# board.net
KiCad netlist of a schematic drawn in EAGLE
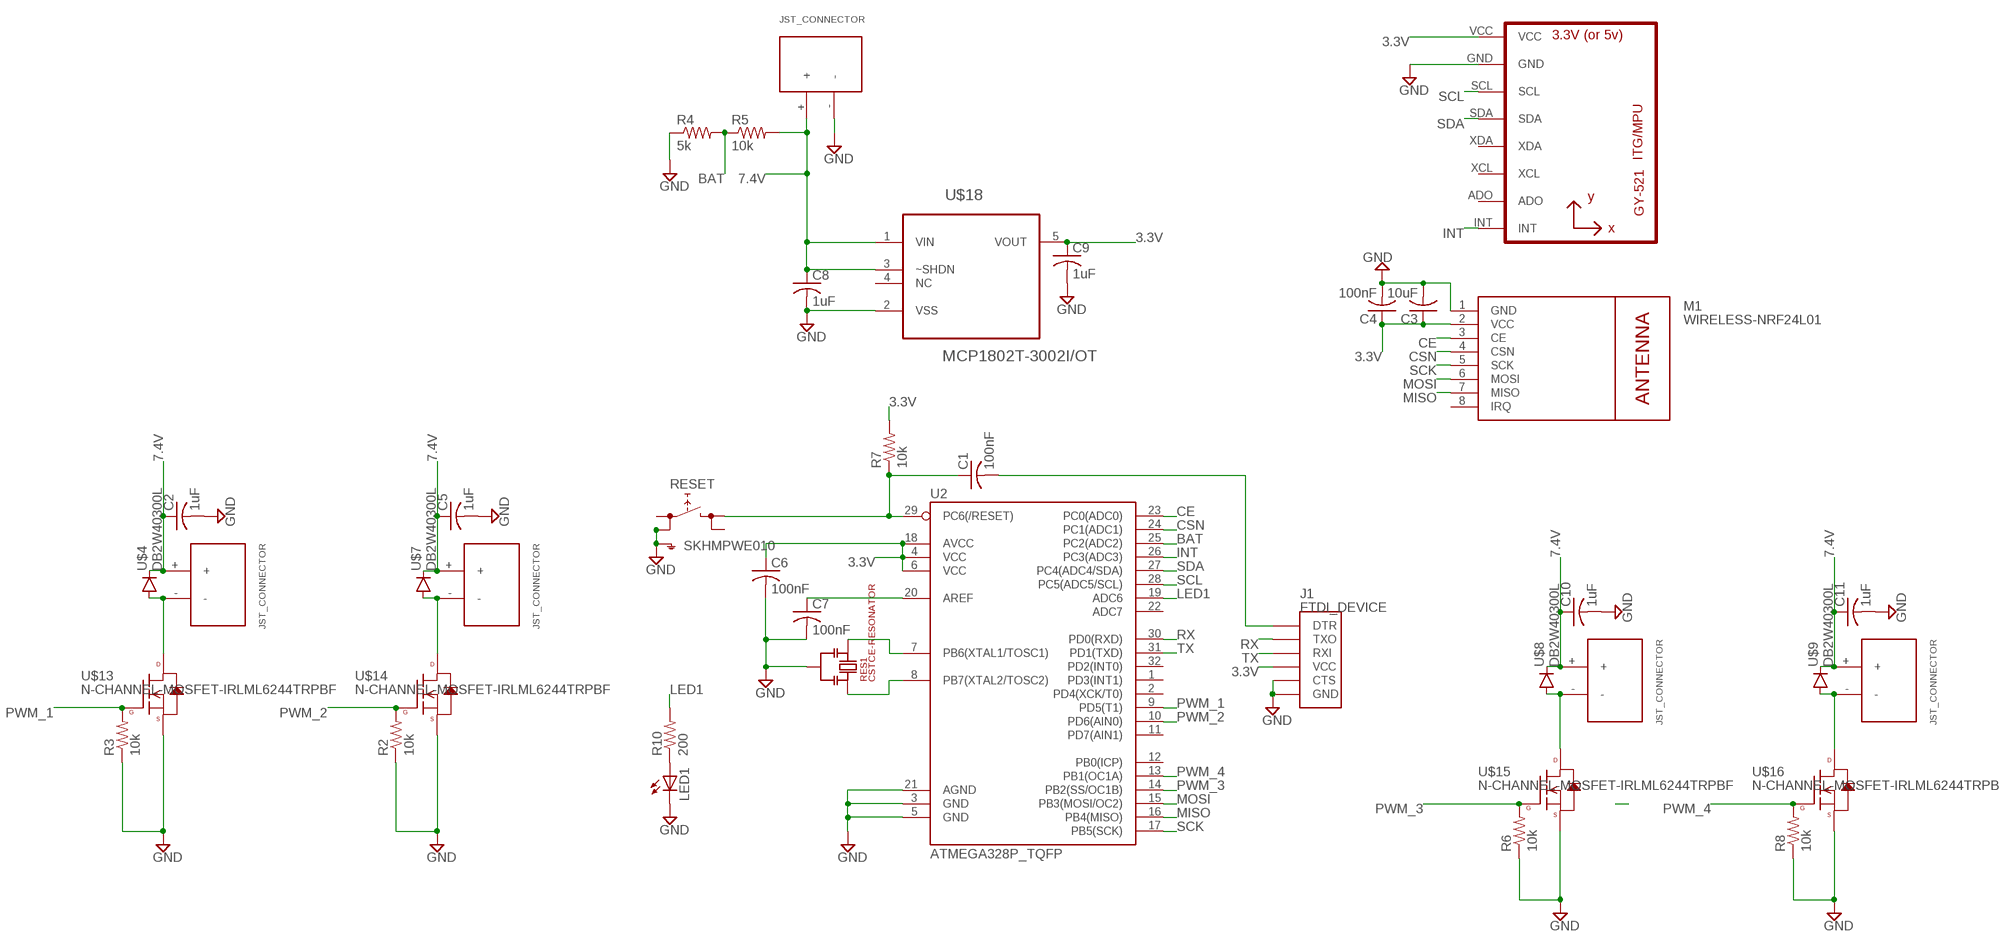
[diagram p0: schematic, sheet 1]

(export (version "E")
  (design (tool "Eeschema 10.0.6"))
  (components
    (comp (ref "C1")
      (value "100nF")
      (footprint "eagle-import:C0603")
      (libsource (lib "eagle-import") (part "C-USC0603"))
    )
    (comp (ref "C2")
      (value "1uF")
      (footprint "eagle-import:C0603")
      (libsource (lib "eagle-import") (part "C-USC0603"))
    )
    (comp (ref "C3")
      (value "10uF")
      (footprint "eagle-import:C0603")
      (libsource (lib "eagle-import") (part "C-USC0603"))
    )
    (comp (ref "C4")
      (value "100nF")
      (footprint "eagle-import:C0603")
      (libsource (lib "eagle-import") (part "C-USC0603"))
    )
    (comp (ref "C5")
      (value "1uF")
      (footprint "eagle-import:C0603")
      (libsource (lib "eagle-import") (part "C-USC0603"))
    )
    (comp (ref "C6")
      (value "100nF")
      (footprint "eagle-import:C0603")
      (libsource (lib "eagle-import") (part "C-USC0603"))
    )
    (comp (ref "C7")
      (value "100nF")
      (footprint "eagle-import:C0603")
      (libsource (lib "eagle-import") (part "C-USC0603"))
    )
    (comp (ref "C8")
      (value "1uF")
      (footprint "eagle-import:C0603")
      (libsource (lib "eagle-import") (part "C-USC0603"))
    )
    (comp (ref "C9")
      (value "1uF")
      (footprint "eagle-import:C0603")
      (libsource (lib "eagle-import") (part "C-USC0603"))
    )
    (comp (ref "C10")
      (value "1uF")
      (footprint "eagle-import:C0603")
      (libsource (lib "eagle-import") (part "C-USC0603"))
    )
    (comp (ref "C11")
      (value "1uF")
      (footprint "eagle-import:C0603")
      (libsource (lib "eagle-import") (part "C-USC0603"))
    )
    (comp (ref "J1")
      (value "FTDI_DEVICE")
      (footprint "eagle-import:FTDI_DEVICE_SIDE")
      (libsource (lib "eagle-import") (part "FTDI_DEVICE"))
    )
    (comp (ref "LED1")
      (value "LEDCHIP-LED0603")
      (footprint "eagle-import:CHIP-LED0603")
      (libsource (lib "eagle-import") (part "LEDCHIP-LED0603"))
    )
    (comp (ref "M1")
      (value "WIRELESS-NRF24L01")
      (footprint "eagle-import:WIRELESS-NRF24L01")
      (libsource (lib "eagle-import") (part "WIRELESS-NRF24L01"))
    )
    (comp (ref "R2")
      (value "10k")
      (footprint "eagle-import:R0603")
      (libsource (lib "eagle-import") (part "R-US_R0603"))
    )
    (comp (ref "R3")
      (value "10k")
      (footprint "eagle-import:R0603")
      (libsource (lib "eagle-import") (part "R-US_R0603"))
    )
    (comp (ref "R4")
      (value "5k")
      (footprint "eagle-import:R0603")
      (libsource (lib "eagle-import") (part "R-US_R0603"))
    )
    (comp (ref "R5")
      (value "10k")
      (footprint "eagle-import:R0603")
      (libsource (lib "eagle-import") (part "R-US_R0603"))
    )
    (comp (ref "R6")
      (value "10k")
      (footprint "eagle-import:R0603")
      (libsource (lib "eagle-import") (part "R-US_R0603"))
    )
    (comp (ref "R7")
      (value "10k")
      (footprint "eagle-import:R0603")
      (libsource (lib "eagle-import") (part "R-US_R0603"))
    )
    (comp (ref "R8")
      (value "10k")
      (footprint "eagle-import:R0603")
      (libsource (lib "eagle-import") (part "R-US_R0603"))
    )
    (comp (ref "R10")
      (value "200")
      (footprint "eagle-import:R0603")
      (libsource (lib "eagle-import") (part "R-US_R0603"))
    )
    (comp (ref "RES1")
      (value "CSTCE-RESONATOR")
      (footprint "eagle-import:CSTCE16M0V53-R0")
      (libsource (lib "eagle-import") (part "CSTCE-RESONATOR"))
    )
    (comp (ref "RESET")
      (value "SKHMPWE010")
      (footprint "eagle-import:SKHMPXE010")
      (libsource (lib "eagle-import") (part "SKHMPE010W"))
    )
    (comp (ref "U$3")
      (value "JST_CONNECTOR_FEMALE")
      (footprint "eagle-import:JST_CONNECTOR_FEMALE")
      (libsource (lib "eagle-import") (part "JST_CONNECTOR_FEMALE"))
    )
    (comp (ref "U$4")
      (value "DB2W40300L")
      (footprint "eagle-import:MINI2-F3-B")
      (libsource (lib "eagle-import") (part "DB2W40300L"))
    )
    (comp (ref "U$7")
      (value "DB2W40300L")
      (footprint "eagle-import:MINI2-F3-B")
      (libsource (lib "eagle-import") (part "DB2W40300L"))
    )
    (comp (ref "U$8")
      (value "DB2W40300L")
      (footprint "eagle-import:MINI2-F3-B")
      (libsource (lib "eagle-import") (part "DB2W40300L"))
    )
    (comp (ref "U$9")
      (value "DB2W40300L")
      (footprint "eagle-import:MINI2-F3-B")
      (libsource (lib "eagle-import") (part "DB2W40300L"))
    )
    (comp (ref "U$10")
      (value "JST_CONNECTOR_FEMALE")
      (footprint "eagle-import:JST_CONNECTOR_FEMALE")
      (libsource (lib "eagle-import") (part "JST_CONNECTOR_FEMALE"))
    )
    (comp (ref "U$11")
      (value "JST_CONNECTOR_FEMALE")
      (footprint "eagle-import:JST_CONNECTOR_FEMALE")
      (libsource (lib "eagle-import") (part "JST_CONNECTOR_FEMALE"))
    )
    (comp (ref "U$12")
      (value "JST_CONNECTOR_FEMALE")
      (footprint "eagle-import:JST_CONNECTOR_FEMALE")
      (libsource (lib "eagle-import") (part "JST_CONNECTOR_FEMALE"))
    )
    (comp (ref "U$13")
      (value "N-CHANNEL-MOSFET-IRLML6244TRPBF")
      (footprint "eagle-import:SOT23-3")
      (libsource (lib "eagle-import") (part "N-CHANNEL-MOSFET-IRLML6244TRPBF"))
    )
    (comp (ref "U$14")
      (value "N-CHANNEL-MOSFET-IRLML6244TRPBF")
      (footprint "eagle-import:SOT23-3")
      (libsource (lib "eagle-import") (part "N-CHANNEL-MOSFET-IRLML6244TRPBF"))
    )
    (comp (ref "U$15")
      (value "N-CHANNEL-MOSFET-IRLML6244TRPBF")
      (footprint "eagle-import:SOT23-3")
      (libsource (lib "eagle-import") (part "N-CHANNEL-MOSFET-IRLML6244TRPBF"))
    )
    (comp (ref "U$16")
      (value "N-CHANNEL-MOSFET-IRLML6244TRPBF")
      (footprint "eagle-import:SOT23-3")
      (libsource (lib "eagle-import") (part "N-CHANNEL-MOSFET-IRLML6244TRPBF"))
    )
    (comp (ref "U$17")
      (value "JST_CONNECTOR_FEMALE")
      (footprint "eagle-import:JST_CONNECTOR_FEMALE")
      (libsource (lib "eagle-import") (part "JST_CONNECTOR_FEMALE"))
    )
    (comp (ref "U$18")
      (value "MCP1802T-3002I/OT")
      (footprint "eagle-import:SOT95P270X145-5N")
      (libsource (lib "eagle-import") (part "MCP1802T-3002I/OT"))
    )
    (comp (ref "U1")
      (value "GY-521MPU6050")
      (footprint "eagle-import:GY-521")
      (libsource (lib "eagle-import") (part "GY-521MPU6050"))
    )
    (comp (ref "U2")
      (value "ATMEGA328P_TQFP")
      (footprint "eagle-import:TQFP32-08")
      (libsource (lib "eagle-import") (part "ATMEGA328P_TQFP"))
    )
  )
  (nets
    (net (code "1") (name "/3.3V") (class "Default")
      (node (ref "C3") (pin "1") (pinfunction "1_1") (pintype "passive"))
      (node (ref "C4") (pin "1") (pinfunction "1_1") (pintype "passive"))
      (node (ref "C6") (pin "1") (pinfunction "1_1") (pintype "passive"))
      (node (ref "C9") (pin "1") (pinfunction "1_1") (pintype "passive"))
      (node (ref "J1") (pin "P$4") (pinfunction "VCC_P$4") (pintype "bidirectional"))
      (node (ref "M1") (pin "2") (pinfunction "VCC_2") (pintype "power_in"))
      (node (ref "R7") (pin "2") (pinfunction "2_2") (pintype "passive"))
      (node (ref "U$18") (pin "5") (pinfunction "VOUT_5") (pintype "output"))
      (node (ref "U1") (pin "VCC") (pinfunction "VCC_VCC") (pintype "bidirectional"))
      (node (ref "U2") (pin "18") (pinfunction "AVCC_18") (pintype "bidirectional"))
      (node (ref "U2") (pin "4") (pinfunction "VCC_4") (pintype "bidirectional"))
      (node (ref "U2") (pin "6") (pinfunction "VCC_6") (pintype "bidirectional"))
    )
    (net (code "2") (name "/7.4V") (class "Default")
      (node (ref "C10") (pin "1") (pinfunction "1_1") (pintype "passive"))
      (node (ref "C11") (pin "1") (pinfunction "1_1") (pintype "passive"))
      (node (ref "C2") (pin "1") (pinfunction "1_1") (pintype "passive"))
      (node (ref "C5") (pin "1") (pinfunction "1_1") (pintype "passive"))
      (node (ref "C8") (pin "1") (pinfunction "1_1") (pintype "passive"))
      (node (ref "R5") (pin "2") (pinfunction "2_2") (pintype "passive"))
      (node (ref "U$10") (pin "+") (pinfunction "+_+") (pintype "bidirectional"))
      (node (ref "U$11") (pin "+") (pinfunction "+_+") (pintype "bidirectional"))
      (node (ref "U$12") (pin "+") (pinfunction "+_+") (pintype "bidirectional"))
      (node (ref "U$17") (pin "+") (pinfunction "+_+") (pintype "bidirectional"))
      (node (ref "U$18") (pin "1") (pinfunction "VIN_1") (pintype "power_in"))
      (node (ref "U$18") (pin "3") (pinfunction "~{SHDN}_3") (pintype "input"))
      (node (ref "U$3") (pin "+") (pinfunction "+_+") (pintype "bidirectional"))
      (node (ref "U$4") (pin "NEG") (pinfunction "GPIN_NEG") (pintype "passive"))
      (node (ref "U$7") (pin "NEG") (pinfunction "GPIN_NEG") (pintype "passive"))
      (node (ref "U$8") (pin "NEG") (pinfunction "GPIN_NEG") (pintype "passive"))
      (node (ref "U$9") (pin "NEG") (pinfunction "GPIN_NEG") (pintype "passive"))
    )
    (net (code "3") (name "/BAT") (class "Default")
      (node (ref "R4") (pin "2") (pinfunction "2_2") (pintype "passive"))
      (node (ref "R5") (pin "1") (pinfunction "1_1") (pintype "passive"))
      (node (ref "U2") (pin "25") (pinfunction "PC2(ADC2)_25") (pintype "bidirectional"))
    )
    (net (code "4") (name "/CE") (class "Default")
      (node (ref "M1") (pin "3") (pinfunction "CE_3") (pintype "bidirectional"))
      (node (ref "U2") (pin "23") (pinfunction "PC0(ADC0)_23") (pintype "bidirectional"))
    )
    (net (code "5") (name "/CSN") (class "Default")
      (node (ref "M1") (pin "4") (pinfunction "CSN_4") (pintype "bidirectional"))
      (node (ref "U2") (pin "24") (pinfunction "PC1(ADC1)_24") (pintype "bidirectional"))
    )
    (net (code "6") (name "/INT") (class "Default")
      (node (ref "U1") (pin "INT") (pinfunction "INT_INT") (pintype "bidirectional"))
      (node (ref "U2") (pin "26") (pinfunction "PC3(ADC3)_26") (pintype "bidirectional"))
    )
    (net (code "7") (name "/LED1") (class "Default")
      (node (ref "R10") (pin "2") (pinfunction "2_2") (pintype "passive"))
      (node (ref "U2") (pin "19") (pinfunction "ADC6_19") (pintype "bidirectional"))
    )
    (net (code "8") (name "/MISO") (class "Default")
      (node (ref "M1") (pin "7") (pinfunction "MISO_7") (pintype "bidirectional"))
      (node (ref "U2") (pin "16") (pinfunction "PB4(MISO)_16") (pintype "bidirectional"))
    )
    (net (code "9") (name "/MOSI") (class "Default")
      (node (ref "M1") (pin "6") (pinfunction "MOSI_6") (pintype "bidirectional"))
      (node (ref "U2") (pin "15") (pinfunction "PB3(MOSI/OC2)_15") (pintype "bidirectional"))
    )
    (net (code "10") (name "/PWM_1") (class "Default")
      (node (ref "R3") (pin "2") (pinfunction "2_2") (pintype "passive"))
      (node (ref "U$13") (pin "1") (pinfunction "G_1") (pintype "passive"))
      (node (ref "U2") (pin "9") (pinfunction "PD5(T1)_9") (pintype "bidirectional"))
    )
    (net (code "11") (name "/PWM_2") (class "Default")
      (node (ref "R2") (pin "2") (pinfunction "2_2") (pintype "passive"))
      (node (ref "U$14") (pin "1") (pinfunction "G_1") (pintype "passive"))
      (node (ref "U2") (pin "10") (pinfunction "PD6(AIN0)_10") (pintype "bidirectional"))
    )
    (net (code "12") (name "/PWM_3") (class "Default")
      (node (ref "R6") (pin "2") (pinfunction "2_2") (pintype "passive"))
      (node (ref "U$15") (pin "1") (pinfunction "G_1") (pintype "passive"))
      (node (ref "U2") (pin "14") (pinfunction "PB2(SS/OC1B)_14") (pintype "bidirectional"))
    )
    (net (code "13") (name "/PWM_4") (class "Default")
      (node (ref "R8") (pin "2") (pinfunction "2_2") (pintype "passive"))
      (node (ref "U$16") (pin "1") (pinfunction "G_1") (pintype "passive"))
      (node (ref "U2") (pin "13") (pinfunction "PB1(OC1A)_13") (pintype "bidirectional"))
    )
    (net (code "14") (name "/RX") (class "Default")
      (node (ref "J1") (pin "P$2") (pinfunction "TXO_P$2") (pintype "bidirectional"))
      (node (ref "U2") (pin "30") (pinfunction "PD0(RXD)_30") (pintype "bidirectional"))
    )
    (net (code "15") (name "/SCK") (class "Default")
      (node (ref "M1") (pin "5") (pinfunction "SCK_5") (pintype "bidirectional"))
      (node (ref "U2") (pin "17") (pinfunction "PB5(SCK)_17") (pintype "bidirectional"))
    )
    (net (code "16") (name "/SCL") (class "Default")
      (node (ref "U1") (pin "SCL") (pinfunction "SCL_SCL") (pintype "bidirectional"))
      (node (ref "U2") (pin "28") (pinfunction "PC5(ADC5/SCL)_28") (pintype "bidirectional"))
    )
    (net (code "17") (name "/SDA") (class "Default")
      (node (ref "U1") (pin "SDA") (pinfunction "SDA_SDA") (pintype "bidirectional"))
      (node (ref "U2") (pin "27") (pinfunction "PC4(ADC4/SDA)_27") (pintype "bidirectional"))
    )
    (net (code "18") (name "/TX") (class "Default")
      (node (ref "J1") (pin "P$3") (pinfunction "RXI_P$3") (pintype "bidirectional"))
      (node (ref "U2") (pin "31") (pinfunction "PD1(TXD)_31") (pintype "bidirectional"))
    )
    (net (code "19") (name "GND") (class "Default")
      (node (ref "C10") (pin "2") (pinfunction "2_2") (pintype "passive"))
      (node (ref "C11") (pin "2") (pinfunction "2_2") (pintype "passive"))
      (node (ref "C2") (pin "2") (pinfunction "2_2") (pintype "passive"))
      (node (ref "C3") (pin "2") (pinfunction "2_2") (pintype "passive"))
      (node (ref "C4") (pin "2") (pinfunction "2_2") (pintype "passive"))
      (node (ref "C5") (pin "2") (pinfunction "2_2") (pintype "passive"))
      (node (ref "C6") (pin "2") (pinfunction "2_2") (pintype "passive"))
      (node (ref "C7") (pin "2") (pinfunction "2_2") (pintype "passive"))
      (node (ref "C8") (pin "2") (pinfunction "2_2") (pintype "passive"))
      (node (ref "C9") (pin "2") (pinfunction "2_2") (pintype "passive"))
      (node (ref "J1") (pin "P$5") (pinfunction "CTS_P$5") (pintype "bidirectional"))
      (node (ref "J1") (pin "P$6") (pinfunction "GND_P$6") (pintype "bidirectional"))
      (node (ref "LED1") (pin "C") (pinfunction "C_C") (pintype "passive"))
      (node (ref "M1") (pin "1") (pinfunction "GND_1") (pintype "power_in"))
      (node (ref "R2") (pin "1") (pinfunction "1_1") (pintype "passive"))
      (node (ref "R3") (pin "1") (pinfunction "1_1") (pintype "passive"))
      (node (ref "R4") (pin "1") (pinfunction "1_1") (pintype "passive"))
      (node (ref "R6") (pin "1") (pinfunction "1_1") (pintype "passive"))
      (node (ref "R8") (pin "1") (pinfunction "1_1") (pintype "passive"))
      (node (ref "RES1") (pin "P$2") (pinfunction "P$2_P$2") (pintype "bidirectional"))
      (node (ref "RESET") (pin "2") (pinfunction "1.2_2") (pintype "passive"))
      (node (ref "RESET") (pin "5") (pinfunction "SH_5") (pintype "passive"))
      (node (ref "U$13") (pin "2") (pinfunction "S_2") (pintype "passive"))
      (node (ref "U$14") (pin "2") (pinfunction "S_2") (pintype "passive"))
      (node (ref "U$15") (pin "2") (pinfunction "S_2") (pintype "passive"))
      (node (ref "U$16") (pin "2") (pinfunction "S_2") (pintype "passive"))
      (node (ref "U$17") (pin "-") (pinfunction "-_-") (pintype "bidirectional"))
      (node (ref "U$18") (pin "2") (pinfunction "VSS_2") (pintype "passive"))
      (node (ref "U1") (pin "GND") (pinfunction "GND_GND") (pintype "bidirectional"))
      (node (ref "U2") (pin "21") (pinfunction "AGND_21") (pintype "bidirectional"))
      (node (ref "U2") (pin "3") (pinfunction "GND_3") (pintype "bidirectional"))
      (node (ref "U2") (pin "5") (pinfunction "GND_5") (pintype "bidirectional"))
    )
    (net (code "20") (name "Net-(J1-DTR)") (class "Default")
      (node (ref "C1") (pin "2") (pinfunction "2_2") (pintype "passive"))
      (node (ref "J1") (pin "P$1") (pinfunction "DTR_P$1") (pintype "bidirectional"))
    )
    (net (code "21") (name "Net-(LED1-PadA)") (class "Default")
      (node (ref "LED1") (pin "A") (pinfunction "A_A") (pintype "passive"))
      (node (ref "R10") (pin "1") (pinfunction "1_1") (pintype "passive"))
    )
    (net (code "22") (name "Net-(RESET-2.1)") (class "Default")
      (node (ref "C1") (pin "1") (pinfunction "1_1") (pintype "passive"))
      (node (ref "R7") (pin "1") (pinfunction "1_1") (pintype "passive"))
      (node (ref "RESET") (pin "3") (pinfunction "2.1_3") (pintype "passive"))
      (node (ref "U2") (pin "29") (pinfunction "PC6(/RESET)_29") (pintype "bidirectional"))
    )
    (net (code "23") (name "Net-(U$13-D)") (class "Default")
      (node (ref "U$13") (pin "3") (pinfunction "D_3") (pintype "passive"))
      (node (ref "U$3") (pin "-") (pinfunction "-_-") (pintype "bidirectional"))
      (node (ref "U$4") (pin "POS") (pinfunction "PPIN_POS") (pintype "passive"))
    )
    (net (code "24") (name "Net-(U$14-D)") (class "Default")
      (node (ref "U$10") (pin "-") (pinfunction "-_-") (pintype "bidirectional"))
      (node (ref "U$14") (pin "3") (pinfunction "D_3") (pintype "passive"))
      (node (ref "U$7") (pin "POS") (pinfunction "PPIN_POS") (pintype "passive"))
    )
    (net (code "25") (name "Net-(U$15-D)") (class "Default")
      (node (ref "U$11") (pin "-") (pinfunction "-_-") (pintype "bidirectional"))
      (node (ref "U$15") (pin "3") (pinfunction "D_3") (pintype "passive"))
      (node (ref "U$8") (pin "POS") (pinfunction "PPIN_POS") (pintype "passive"))
    )
    (net (code "26") (name "Net-(U$16-D)") (class "Default")
      (node (ref "U$12") (pin "-") (pinfunction "-_-") (pintype "bidirectional"))
      (node (ref "U$16") (pin "3") (pinfunction "D_3") (pintype "passive"))
      (node (ref "U$9") (pin "POS") (pinfunction "PPIN_POS") (pintype "passive"))
    )
    (net (code "27") (name "Net-(U2-AREF)") (class "Default")
      (node (ref "C7") (pin "1") (pinfunction "1_1") (pintype "passive"))
      (node (ref "U2") (pin "20") (pinfunction "AREF_20") (pintype "bidirectional"))
    )
    (net (code "28") (name "Net-(U2-PB6(XTAL1{slash}TOSC1))") (class "Default")
      (node (ref "RES1") (pin "P$3") (pinfunction "P$3_P$3") (pintype "bidirectional"))
      (node (ref "U2") (pin "7") (pinfunction "PB6(XTAL1/TOSC1)_7") (pintype "bidirectional"))
    )
    (net (code "29") (name "Net-(U2-PB7(XTAL2{slash}TOSC2))") (class "Default")
      (node (ref "RES1") (pin "P$1") (pinfunction "P$1_P$1") (pintype "bidirectional"))
      (node (ref "U2") (pin "8") (pinfunction "PB7(XTAL2/TOSC2)_8") (pintype "bidirectional"))
    )
    (net (code "30") (name "unconnected-(M1-IRQ-Pad8)") (class "Default")
      (node (ref "M1") (pin "8") (pinfunction "IRQ_8") (pintype "bidirectional"))
    )
    (net (code "31") (name "unconnected-(RESET-1.1-Pad1)") (class "Default")
      (node (ref "RESET") (pin "1") (pinfunction "1.1_1") (pintype "passive"))
    )
    (net (code "32") (name "unconnected-(RESET-2.2-Pad4)") (class "Default")
      (node (ref "RESET") (pin "4") (pinfunction "2.2_4") (pintype "passive"))
    )
    (net (code "33") (name "unconnected-(U$18-NC-Pad4)") (class "Default")
      (node (ref "U$18") (pin "4") (pinfunction "NC_4") (pintype "no_connect"))
    )
    (net (code "34") (name "unconnected-(U1-PadADO)") (class "Default")
      (node (ref "U1") (pin "ADO") (pinfunction "ADO_ADO") (pintype "bidirectional"))
    )
    (net (code "35") (name "unconnected-(U1-PadXCL)") (class "Default")
      (node (ref "U1") (pin "XCL") (pinfunction "XCL_XCL") (pintype "bidirectional"))
    )
    (net (code "36") (name "unconnected-(U1-PadXDA)") (class "Default")
      (node (ref "U1") (pin "XDA") (pinfunction "XDA_XDA") (pintype "bidirectional"))
    )
    (net (code "37") (name "unconnected-(U2-ADC7-Pad22)") (class "Default")
      (node (ref "U2") (pin "22") (pinfunction "ADC7_22") (pintype "bidirectional"))
    )
    (net (code "38") (name "unconnected-(U2-PB0(ICP)-Pad12)") (class "Default")
      (node (ref "U2") (pin "12") (pinfunction "PB0(ICP)_12") (pintype "bidirectional"))
    )
    (net (code "39") (name "unconnected-(U2-PD2(INT0)-Pad32)") (class "Default")
      (node (ref "U2") (pin "32") (pinfunction "PD2(INT0)_32") (pintype "bidirectional"))
    )
    (net (code "40") (name "unconnected-(U2-PD3(INT1)-Pad1)") (class "Default")
      (node (ref "U2") (pin "1") (pinfunction "PD3(INT1)_1") (pintype "bidirectional"))
    )
    (net (code "41") (name "unconnected-(U2-PD4(XCK{slash}T0)-Pad2)") (class "Default")
      (node (ref "U2") (pin "2") (pinfunction "PD4(XCK/T0)_2") (pintype "bidirectional"))
    )
    (net (code "42") (name "unconnected-(U2-PD7(AIN1)-Pad11)") (class "Default")
      (node (ref "U2") (pin "11") (pinfunction "PD7(AIN1)_11") (pintype "bidirectional"))
    )
  )
)
